# 6___RS485_RS232.net
KiCad netlist of a schematic drawn in Altium Designer
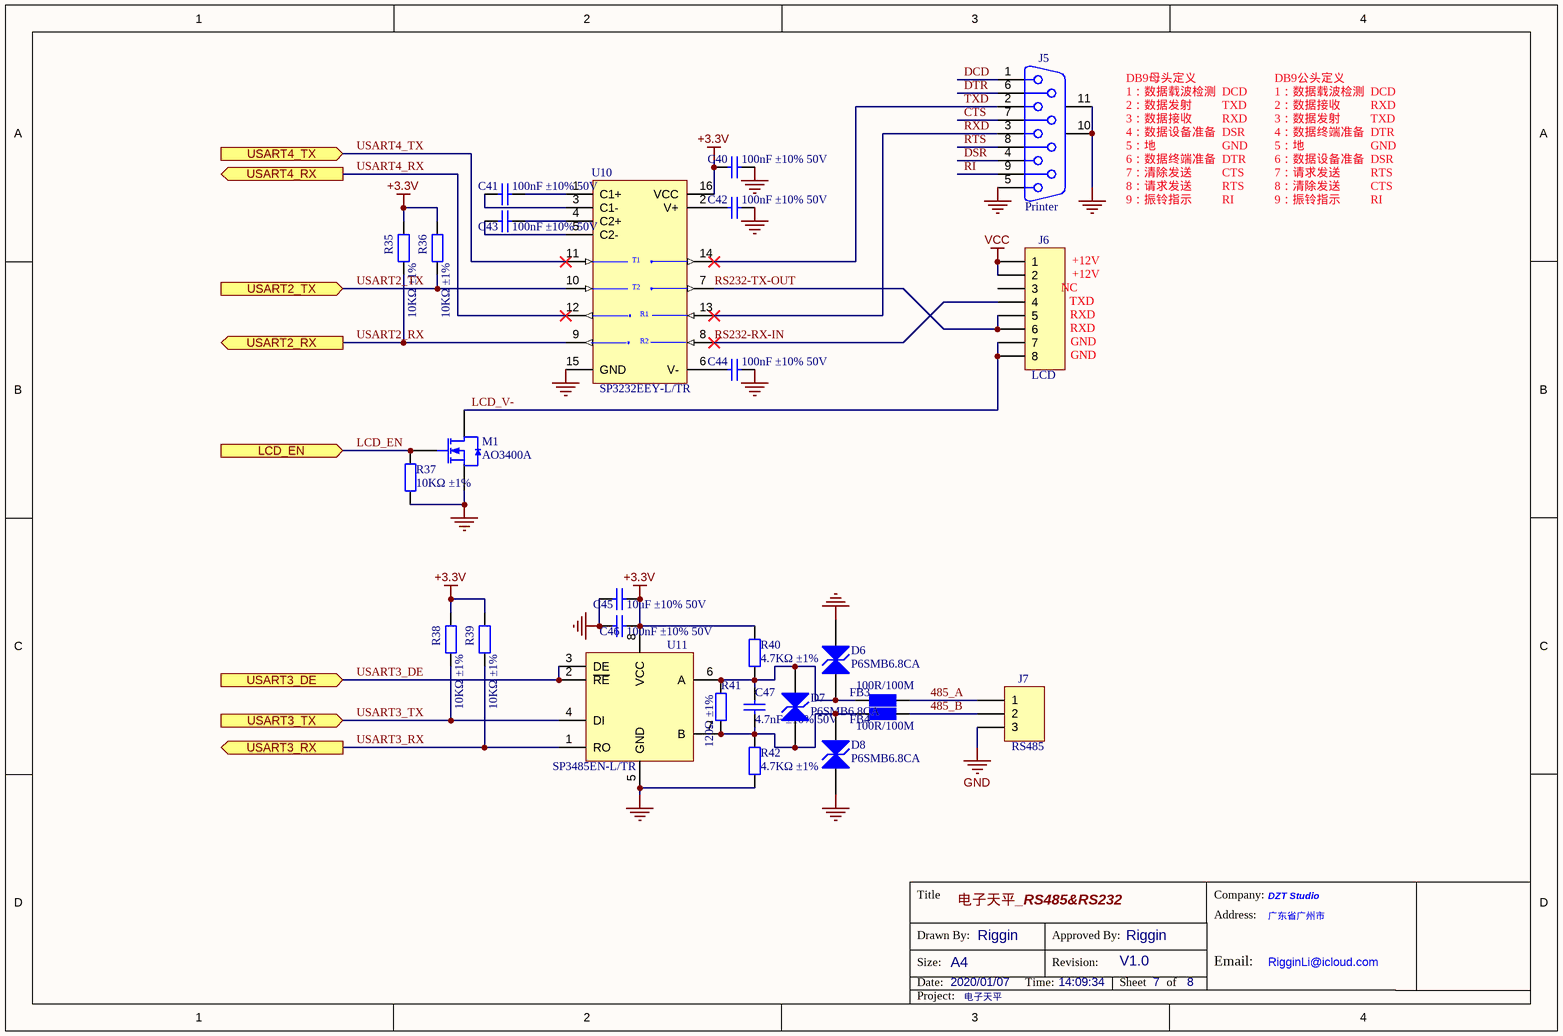
[diagram p0: 6_电子天平_RS485&RS232.SchDoc]

(export (version "E")
  (design (tool "Eeschema 10.0.6"))
  (components
    (comp (ref "C40")
      (value "100nF ±10% 50V")
      (footprint "LC-0603_C")
      (description "MLCC")
      (fields (field (name "PUBLISHER") "Altium Limited"))
      (libsource (lib "Miscellaneous Devices") (part "Cap"))
    )
    (comp (ref "C41")
      (value "100nF ±10% 50V")
      (footprint "LC-0603_C")
      (description "MLCC")
      (fields (field (name "PUBLISHER") "Altium Limited"))
      (libsource (lib "Miscellaneous Devices") (part "Cap"))
    )
    (comp (ref "C42")
      (value "100nF ±10% 50V")
      (footprint "LC-0603_C")
      (description "MLCC")
      (fields (field (name "PUBLISHER") "Altium Limited"))
      (libsource (lib "Miscellaneous Devices") (part "Cap"))
    )
    (comp (ref "C43")
      (value "100nF ±10% 50V")
      (footprint "LC-0603_C")
      (description "MLCC")
      (fields (field (name "PUBLISHER") "Altium Limited"))
      (libsource (lib "Miscellaneous Devices") (part "Cap"))
    )
    (comp (ref "C44")
      (value "100nF ±10% 50V")
      (footprint "LC-0603_C")
      (description "MLCC")
      (fields (field (name "PUBLISHER") "Altium Limited"))
      (libsource (lib "Miscellaneous Devices") (part "Cap"))
    )
    (comp (ref "C45")
      (value "10uF ±10% 50V")
      (footprint "LC-1206_C")
      (description "MLCC")
      (fields (field (name "PUBLISHER") "Altium Limited"))
      (libsource (lib "Miscellaneous Devices") (part "Cap"))
    )
    (comp (ref "C46")
      (value "100nF ±10% 50V")
      (footprint "LC-0805_C")
      (description "MLCC")
      (fields (field (name "PUBLISHER") "Altium Limited"))
      (libsource (lib "Miscellaneous Devices") (part "Cap"))
    )
    (comp (ref "C47")
      (value "4.7nF ±10% 50V")
      (footprint "LC-0805_C")
      (description "MLCC")
      (fields (field (name "PUBLISHER") "Altium Limited"))
      (libsource (lib "Miscellaneous Devices") (part "Cap"))
    )
    (comp (ref "D6")
      (value "P6SMB6.8CA")
      (footprint "LC-SMB(DO-214AA)_S1")
      (description "TVS")
      (libsource (lib "Miscellaneous Devices LC") (part "SMB/DO-214AA P6SMB6.8CA"))
    )
    (comp (ref "D7")
      (value "P6SMB6.8CA")
      (footprint "LC-SMB(DO-214AA)_S1")
      (description "TVS")
      (libsource (lib "Miscellaneous Devices LC") (part "SMB/DO-214AA P6SMB6.8CA"))
    )
    (comp (ref "D8")
      (value "P6SMB6.8CA")
      (footprint "LC-SMB(DO-214AA)_S1")
      (description "TVS")
      (libsource (lib "Miscellaneous Devices LC") (part "SMB/DO-214AA P6SMB6.8CA"))
    )
    (comp (ref "FB3")
      (value "100R/100M")
      (footprint "LC-0805_L")
      (description "磁珠")
      (libsource (lib "Riggin") (part "FB"))
    )
    (comp (ref "FB4")
      (value "100R/100M")
      (footprint "LC-0805_L")
      (description "磁珠")
      (libsource (lib "Riggin") (part "FB"))
    )
    (comp (ref "J5")
      (value "Printer")
      (footprint "CON-DB9_Female")
      (description "Receptacle Assembly, 9 Position, Right Angle")
      (fields (field (name "PUBLISHER") "Altium Limited"))
      (libsource (lib "Miscellaneous Connectors") (part "D Connector 9"))
    )
    (comp (ref "J6")
      (value "LCD")
      (footprint "CON-A2505WR-8P")
      (description "Header, 8-Pin, Right Angle")
      (fields (field (name "PUBLISHER") "Altium Limited"))
      (libsource (lib "Miscellaneous Connectors") (part "Header 8H"))
    )
    (comp (ref "J7")
      (value "RS485")
      (description "Header, 3-Pin")
      (fields (field (name "PUBLISHER") "Altium Limited"))
      (libsource (lib "Miscellaneous Connectors") (part "Header 3"))
    )
    (comp (ref "M1")
      (value "AO3400A")
      (footprint "LC-SOT-23(SOT-23-3)")
      (description "MOS(场效应管)")
      (libsource (lib "Miscellaneous Devices LC") (part "AO3400A N道沟 X0YV1T SOT-23"))
    )
    (comp (ref "R35")
      (value "10KΩ ±1%")
      (footprint "LC-0805_R")
      (description "Resistor")
      (fields (field (name "PUBLISHER") "Altium Limited"))
      (libsource (lib "Miscellaneous Devices") (part "Res2"))
    )
    (comp (ref "R36")
      (value "10KΩ ±1%")
      (footprint "LC-0805_R")
      (description "Resistor")
      (fields (field (name "PUBLISHER") "Altium Limited"))
      (libsource (lib "Miscellaneous Devices") (part "Res2"))
    )
    (comp (ref "R37")
      (value "10KΩ ±1%")
      (footprint "LC-0805_R")
      (description "Resistor")
      (fields (field (name "PUBLISHER") "Altium Limited"))
      (libsource (lib "Miscellaneous Devices") (part "Res2"))
    )
    (comp (ref "R38")
      (value "10KΩ ±1%")
      (footprint "LC-0805_R")
      (description "Resistor")
      (fields (field (name "PUBLISHER") "Altium Limited"))
      (libsource (lib "Miscellaneous Devices") (part "Res2"))
    )
    (comp (ref "R39")
      (value "10KΩ ±1%")
      (footprint "LC-0805_R")
      (description "Resistor")
      (fields (field (name "PUBLISHER") "Altium Limited"))
      (libsource (lib "Miscellaneous Devices") (part "Res2"))
    )
    (comp (ref "R40")
      (value "4.7KΩ ±1%")
      (footprint "LC-0805_R")
      (description "Resistor")
      (fields (field (name "PUBLISHER") "Altium Limited"))
      (libsource (lib "") (part "Res2_1"))
    )
    (comp (ref "R41")
      (value "120Ω ±1%")
      (footprint "LC-0805_R")
      (description "Resistor")
      (fields (field (name "PUBLISHER") "Altium Limited"))
      (libsource (lib "") (part "Res2_1"))
    )
    (comp (ref "R42")
      (value "4.7KΩ ±1%")
      (footprint "LC-0805_R")
      (description "Resistor")
      (fields (field (name "PUBLISHER") "Altium Limited"))
      (libsource (lib "") (part "Res2_1"))
    )
    (comp (ref "U10")
      (value "SP3232EEY-L/TR")
      (footprint "LC-TSSOP-16")
      (description "+5V-Powered, Multichannel RS-232 Driver/Receiver")
      (fields (field (name "PUBLISHER") "Altium Limited"))
      (libsource (lib "Maxim Communication Transceiver") (part "MAX232AESE"))
    )
    (comp (ref "U11")
      (value "SP3485EN-L/TR")
      (footprint "LC-SOIC-8_150mil")
      (description "RS485")
      (libsource (lib "MyDesign") (part "SP3485EN"))
    )
  )
  (nets
    (net (code "1") (name "+3.3V") (class "Default")
      (node (ref "C40") (pin "2") (pinfunction "2_2") (pintype "passive"))
      (node (ref "C45") (pin "2") (pinfunction "2_2") (pintype "passive"))
      (node (ref "C46") (pin "1") (pinfunction "1_1") (pintype "passive"))
      (node (ref "R35") (pin "1") (pinfunction "1_1") (pintype "passive"))
      (node (ref "R36") (pin "1") (pinfunction "1_1") (pintype "passive"))
      (node (ref "R38") (pin "1") (pinfunction "1_1") (pintype "passive"))
      (node (ref "R39") (pin "1") (pinfunction "1_1") (pintype "passive"))
      (node (ref "R40") (pin "2") (pinfunction "2_2") (pintype "passive"))
      (node (ref "U10") (pin "16") (pinfunction "VCC_16") (pintype "power_in"))
      (node (ref "U11") (pin "8") (pinfunction "VCC_8") (pintype "passive"))
    )
    (net (code "2") (name "/485_A") (class "Default")
      (node (ref "FB3") (pin "1") (pinfunction "1_1") (pintype "passive"))
      (node (ref "J7") (pin "1") (pinfunction "1_1") (pintype "passive"))
    )
    (net (code "3") (name "/485_B") (class "Default")
      (node (ref "FB4") (pin "1") (pinfunction "1_1") (pintype "passive"))
      (node (ref "J7") (pin "2") (pinfunction "2_2") (pintype "passive"))
    )
    (net (code "4") (name "/CTS") (class "Default")
      (node (ref "J5") (pin "7") (pinfunction "7_7") (pintype "passive"))
    )
    (net (code "5") (name "/DCD") (class "Default")
      (node (ref "J5") (pin "1") (pinfunction "1_1") (pintype "passive"))
    )
    (net (code "6") (name "/DSR") (class "Default")
      (node (ref "J5") (pin "4") (pinfunction "4_4") (pintype "passive"))
    )
    (net (code "7") (name "/DTR") (class "Default")
      (node (ref "J5") (pin "6") (pinfunction "6_6") (pintype "passive"))
    )
    (net (code "8") (name "/LCD_EN") (class "Default")
      (node (ref "M1") (pin "1") (pinfunction "G_1") (pintype "passive"))
      (node (ref "R37") (pin "1") (pinfunction "1_1") (pintype "passive"))
    )
    (net (code "9") (name "/LCD_V-") (class "Default")
      (node (ref "J6") (pin "7") (pinfunction "7_7") (pintype "passive"))
      (node (ref "J6") (pin "8") (pinfunction "8_8") (pintype "passive"))
      (node (ref "M1") (pin "3") (pinfunction "D_3") (pintype "passive"))
    )
    (net (code "10") (name "/RI") (class "Default")
      (node (ref "J5") (pin "9") (pinfunction "9_9") (pintype "passive"))
    )
    (net (code "11") (name "/RS232-RX-IN") (class "Default")
      (node (ref "J6") (pin "4") (pinfunction "4_4") (pintype "passive"))
      (node (ref "U10") (pin "8") (pinfunction "R2IN_8") (pintype "input"))
    )
    (net (code "12") (name "/RS232-TX-OUT") (class "Default")
      (node (ref "J6") (pin "5") (pinfunction "5_5") (pintype "passive"))
      (node (ref "J6") (pin "6") (pinfunction "6_6") (pintype "passive"))
      (node (ref "U10") (pin "7") (pinfunction "T2OUT_7") (pintype "output"))
    )
    (net (code "13") (name "/RTS") (class "Default")
      (node (ref "J5") (pin "8") (pinfunction "8_8") (pintype "passive"))
    )
    (net (code "14") (name "/RXD") (class "Default")
      (node (ref "J5") (pin "3") (pinfunction "3_3") (pintype "passive"))
      (node (ref "U10") (pin "13") (pinfunction "R1IN_13") (pintype "input"))
    )
    (net (code "15") (name "/TXD") (class "Default")
      (node (ref "J5") (pin "2") (pinfunction "2_2") (pintype "passive"))
      (node (ref "U10") (pin "14") (pinfunction "T1OUT_14") (pintype "output"))
    )
    (net (code "16") (name "/USART2_RX") (class "Default")
      (node (ref "R35") (pin "2") (pinfunction "2_2") (pintype "passive"))
      (node (ref "U10") (pin "9") (pinfunction "R2OUT_9") (pintype "output"))
    )
    (net (code "17") (name "/USART2_TX") (class "Default")
      (node (ref "R36") (pin "2") (pinfunction "2_2") (pintype "passive"))
      (node (ref "U10") (pin "10") (pinfunction "T2IN_10") (pintype "input"))
    )
    (net (code "18") (name "/USART3_DE") (class "Default")
      (node (ref "U11") (pin "2") (pinfunction "~{RE}_2") (pintype "passive"))
      (node (ref "U11") (pin "3") (pinfunction "DE_3") (pintype "passive"))
    )
    (net (code "19") (name "/USART3_RX") (class "Default")
      (node (ref "R39") (pin "2") (pinfunction "2_2") (pintype "passive"))
      (node (ref "U11") (pin "1") (pinfunction "RO_1") (pintype "passive"))
    )
    (net (code "20") (name "/USART3_TX") (class "Default")
      (node (ref "R38") (pin "2") (pinfunction "2_2") (pintype "passive"))
      (node (ref "U11") (pin "4") (pinfunction "DI_4") (pintype "passive"))
    )
    (net (code "21") (name "/USART4_RX") (class "Default")
      (node (ref "U10") (pin "12") (pinfunction "R1OUT_12") (pintype "output+no_connect"))
    )
    (net (code "22") (name "/USART4_TX") (class "Default")
      (node (ref "U10") (pin "11") (pinfunction "T1IN_11") (pintype "input+no_connect"))
    )
    (net (code "23") (name "GND") (class "Default")
      (node (ref "C40") (pin "1") (pinfunction "1_1") (pintype "passive"))
      (node (ref "C42") (pin "2") (pinfunction "2_2") (pintype "passive"))
      (node (ref "C44") (pin "2") (pinfunction "2_2") (pintype "passive"))
      (node (ref "C45") (pin "1") (pinfunction "1_1") (pintype "passive"))
      (node (ref "C46") (pin "2") (pinfunction "2_2") (pintype "passive"))
      (node (ref "D6") (pin "1") (pinfunction "A_1") (pintype "passive"))
      (node (ref "D8") (pin "1") (pinfunction "A_1") (pintype "passive"))
      (node (ref "J5") (pin "10") (pinfunction "MH1_10") (pintype "passive"))
      (node (ref "J5") (pin "11") (pinfunction "MH2_11") (pintype "passive"))
      (node (ref "J5") (pin "5") (pinfunction "5_5") (pintype "passive"))
      (node (ref "J7") (pin "3") (pinfunction "3_3") (pintype "passive"))
      (node (ref "M1") (pin "2") (pinfunction "S_2") (pintype "passive"))
      (node (ref "R37") (pin "2") (pinfunction "2_2") (pintype "passive"))
      (node (ref "R42") (pin "1") (pinfunction "1_1") (pintype "passive"))
      (node (ref "U10") (pin "15") (pinfunction "GND_15") (pintype "power_in"))
      (node (ref "U11") (pin "5") (pinfunction "GND_5") (pintype "passive"))
    )
    (net (code "24") (name "Net-(D6-K)") (class "Default")
      (node (ref "C47") (pin "2") (pinfunction "2_2") (pintype "passive"))
      (node (ref "D6") (pin "2") (pinfunction "K_2") (pintype "passive"))
      (node (ref "D7") (pin "1") (pinfunction "A_1") (pintype "passive"))
      (node (ref "FB3") (pin "2") (pinfunction "2_2") (pintype "passive"))
      (node (ref "R40") (pin "1") (pinfunction "1_1") (pintype "passive"))
      (node (ref "R41") (pin "2") (pinfunction "2_2") (pintype "passive"))
      (node (ref "U11") (pin "6") (pinfunction "A_6") (pintype "passive"))
    )
    (net (code "25") (name "Net-(D7-K)") (class "Default")
      (node (ref "C47") (pin "1") (pinfunction "1_1") (pintype "passive"))
      (node (ref "D7") (pin "2") (pinfunction "K_2") (pintype "passive"))
      (node (ref "D8") (pin "2") (pinfunction "K_2") (pintype "passive"))
      (node (ref "FB4") (pin "2") (pinfunction "2_2") (pintype "passive"))
      (node (ref "R41") (pin "1") (pinfunction "1_1") (pintype "passive"))
      (node (ref "R42") (pin "2") (pinfunction "2_2") (pintype "passive"))
      (node (ref "U11") (pin "7") (pinfunction "B_7") (pintype "passive"))
    )
    (net (code "26") (name "Net-(U10-C1+)") (class "Default")
      (node (ref "C41") (pin "2") (pinfunction "2_2") (pintype "passive"))
      (node (ref "U10") (pin "1") (pinfunction "C1+_1") (pintype "passive"))
    )
    (net (code "27") (name "Net-(U10-C1-)") (class "Default")
      (node (ref "C41") (pin "1") (pinfunction "1_1") (pintype "passive"))
      (node (ref "U10") (pin "3") (pinfunction "C1-_3") (pintype "passive"))
    )
    (net (code "28") (name "Net-(U10-C2+)") (class "Default")
      (node (ref "C43") (pin "2") (pinfunction "2_2") (pintype "passive"))
      (node (ref "U10") (pin "4") (pinfunction "C2+_4") (pintype "passive"))
    )
    (net (code "29") (name "Net-(U10-C2-)") (class "Default")
      (node (ref "C43") (pin "1") (pinfunction "1_1") (pintype "passive"))
      (node (ref "U10") (pin "5") (pinfunction "C2-_5") (pintype "passive"))
    )
    (net (code "30") (name "Net-(U10-V+)") (class "Default")
      (node (ref "C42") (pin "1") (pinfunction "1_1") (pintype "passive"))
      (node (ref "U10") (pin "2") (pinfunction "V+_2") (pintype "power_in"))
    )
    (net (code "31") (name "Net-(U10-V-)") (class "Default")
      (node (ref "C44") (pin "1") (pinfunction "1_1") (pintype "passive"))
      (node (ref "U10") (pin "6") (pinfunction "V-_6") (pintype "power_in"))
    )
    (net (code "32") (name "VCC") (class "Default")
      (node (ref "J6") (pin "1") (pinfunction "1_1") (pintype "passive"))
      (node (ref "J6") (pin "2") (pinfunction "2_2") (pintype "passive"))
    )
    (net (code "33") (name "unconnected-(J6-Pad3)") (class "Default")
      (node (ref "J6") (pin "3") (pinfunction "3_3") (pintype "passive"))
    )
  )
)
